# Sheet4.net
KiCad netlist of a schematic drawn in Altium Designer
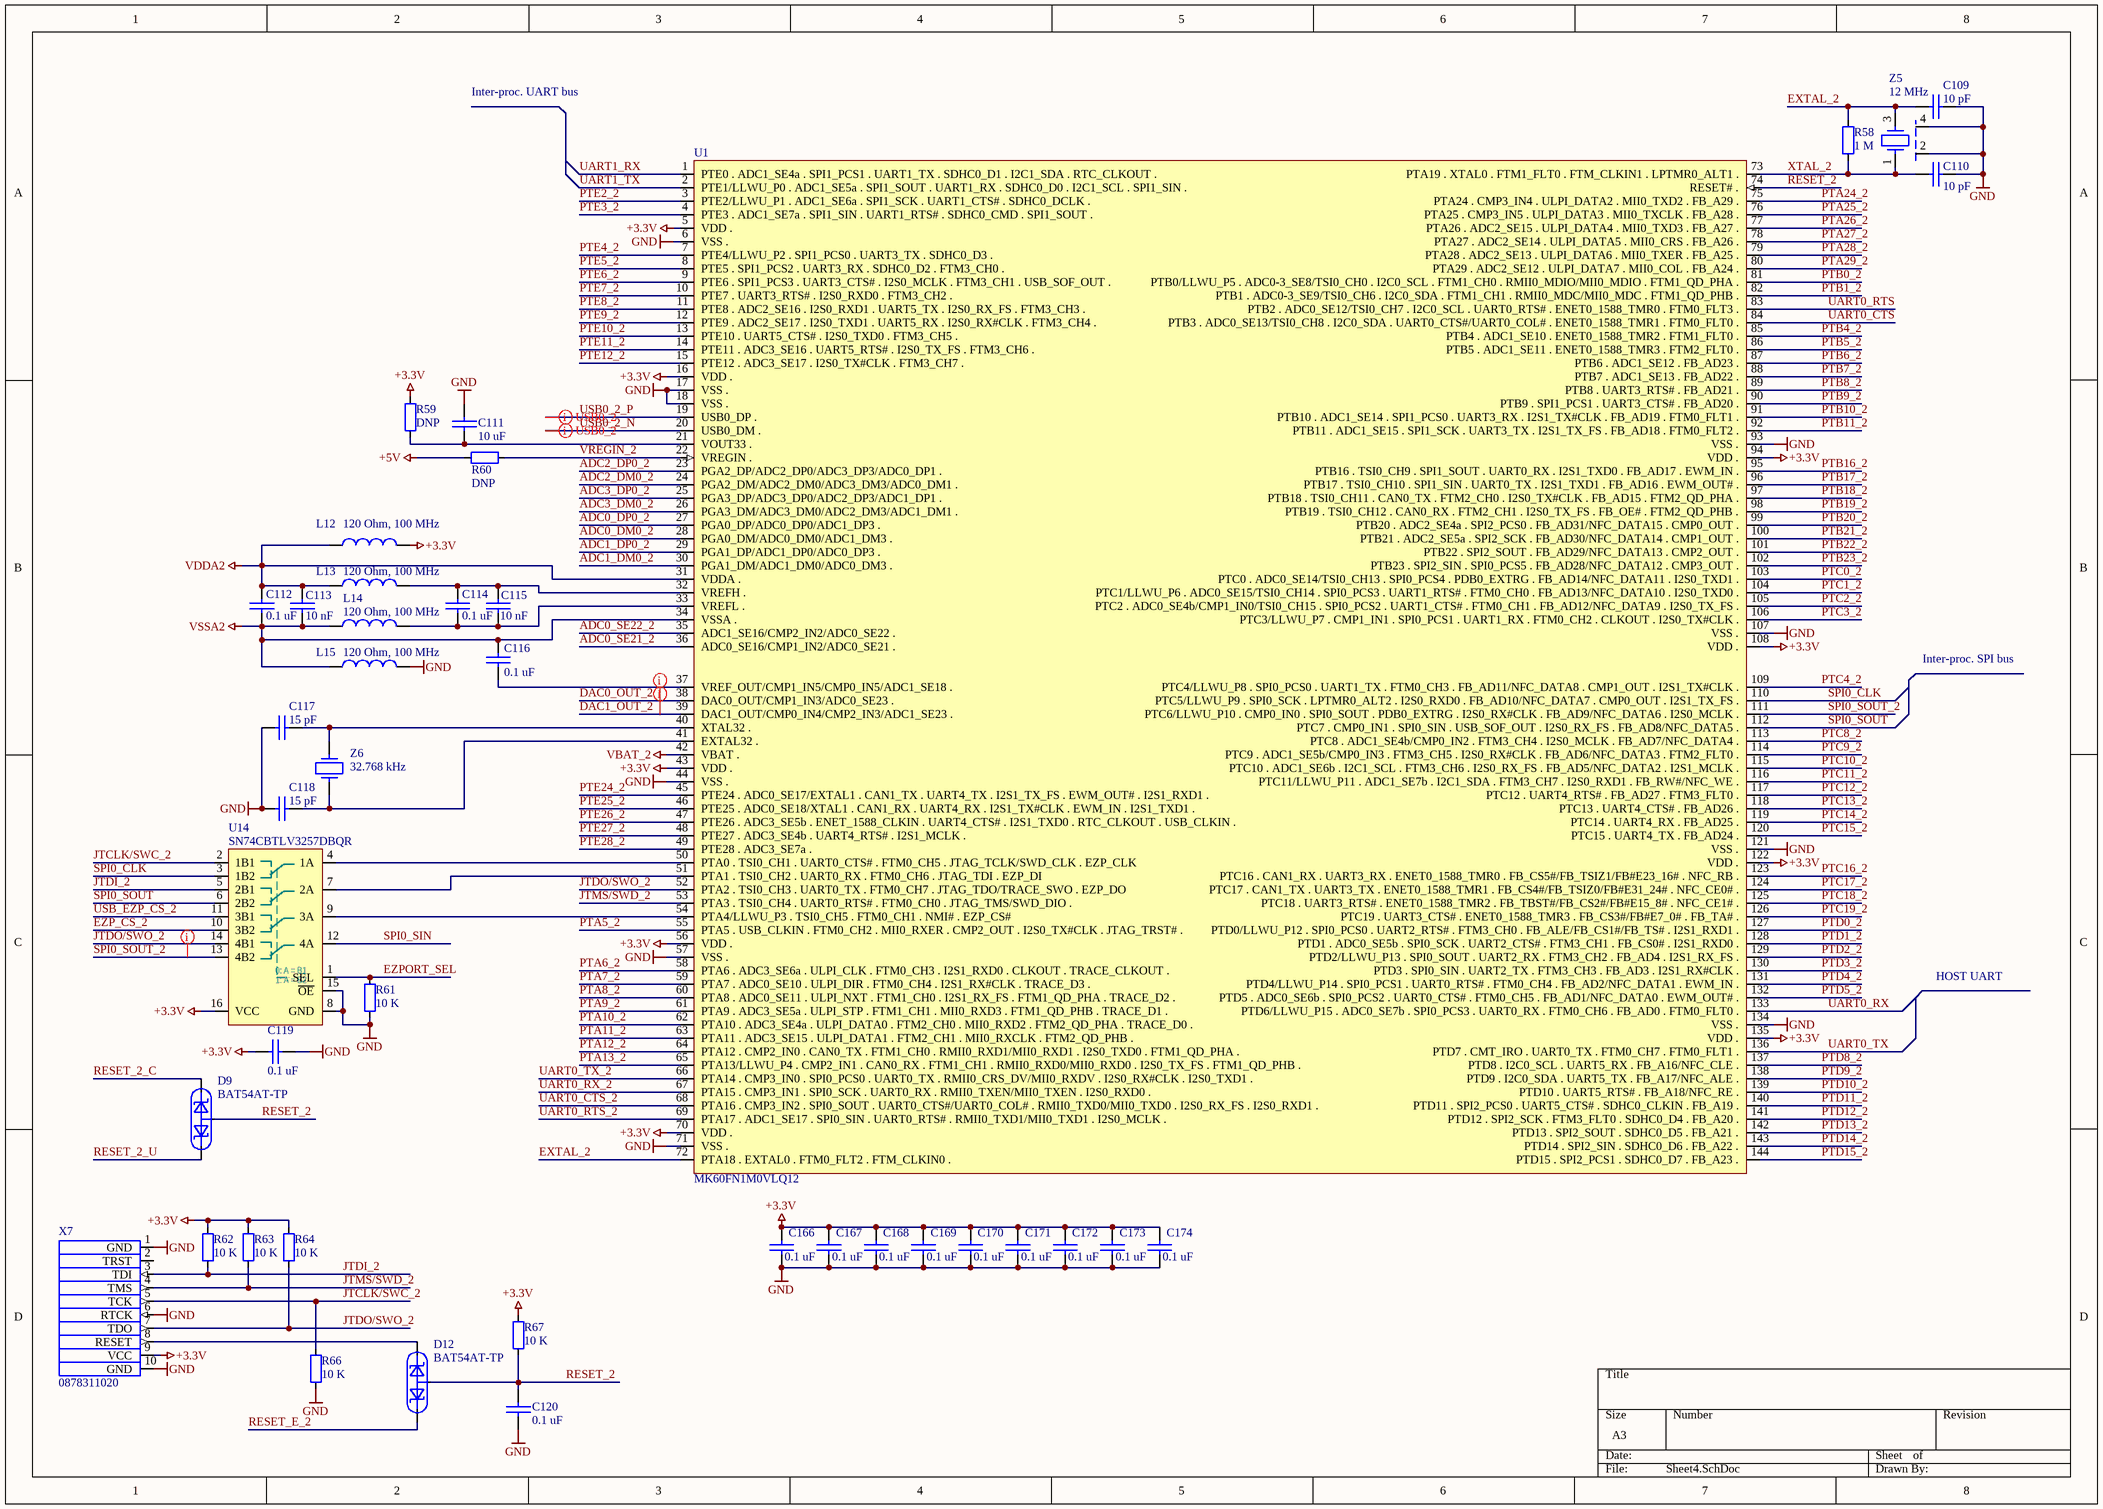
[diagram p0: Sheet4.SchDoc]

(export (version "E")
  (design (tool "Eeschema 10.0.6"))
  (components
    (comp (ref "C109")
      (value "10 pF")
      (footprint "1608[0603]")
      (description "10 pF, 50V, 5%, NP0, 0603 SMD MLC Capacitor")
      (fields (field (name "MANUFACTURER") "Kemet") (field (name "TOLERANCE") "5%"))
      (libsource (lib "ea_Capacitors") (part "CCPF010K0603"))
    )
    (comp (ref "C110")
      (value "10 pF")
      (footprint "1608[0603]")
      (description "10 pF, 50V, 5%, NP0, 0603 SMD MLC Capacitor")
      (fields (field (name "MANUFACTURER") "Kemet") (field (name "TOLERANCE") "5%"))
      (libsource (lib "ea_Capacitors") (part "CCPF010K0603"))
    )
    (comp (ref "C111")
      (value "10 uF")
      (footprint "2012[0805]")
      (description "10 uF, 16V, X5R, ±10%, 0805")
      (fields (field (name "MANUFACTURER") "TDK Corporation") (field (name "TOLERANCE") "±10%"))
      (libsource (lib "ea_Capacitors") (part "C2012X5R1C106K/0.85"))
    )
    (comp (ref "C112")
      (value "0.1 uF")
      (footprint "1005[0402]")
      (description "0.1 uF, 16V, 10%, X7R, 0402")
      (fields (field (name "TOLERANCE") "10%") (field (name "MANUFACTURER") "Murata"))
      (libsource (lib "ea_Capacitors") (part "GRM155R71C104KA88D"))
    )
    (comp (ref "C113")
      (value "10 nF")
      (footprint "1005[0402]")
      (description "10 nF, 16V, 10%, X7R, 0402")
      (fields (field (name "TOLERANCE") "10%") (field (name "MANUFACTURER") "SAMSUNG"))
      (libsource (lib "ea_Capacitors") (part "GRM155R71C103KA01D_1"))
    )
    (comp (ref "C114")
      (value "0.1 uF")
      (footprint "1005[0402]")
      (description "0.1 uF, 16V, 10%, X7R, 0402")
      (fields (field (name "TOLERANCE") "10%") (field (name "MANUFACTURER") "Murata"))
      (libsource (lib "ea_Capacitors") (part "GRM155R71C104KA88D"))
    )
    (comp (ref "C115")
      (value "10 nF")
      (footprint "1005[0402]")
      (description "10 nF, 16V, 10%, X7R, 0402")
      (fields (field (name "TOLERANCE") "10%") (field (name "MANUFACTURER") "SAMSUNG"))
      (libsource (lib "ea_Capacitors") (part "GRM155R71C103KA01D_1"))
    )
    (comp (ref "C116")
      (value "0.1 uF")
      (footprint "1608[0603]")
      (description "0.1 uF, 25V, 10% , X7R,  0603 SMD MLC Capacitor")
      (fields (field (name "TOLERANCE") "10%") (field (name "MANUFACTURER") "SAMSUNG"))
      (libsource (lib "ea_Capacitors") (part "CVNF100K0603-25"))
    )
    (comp (ref "C117")
      (value "15 pF")
      (footprint "1608[0603]")
      (description "15 pF, 50V, 5%, NP0, 0603 SMD MLC Capacitor")
      (fields (field (name "MANUFACTURER") "YAGEO AMERICA CORPORATION") (field (name "TOLERANCE") "5%"))
      (libsource (lib "ea_Capacitors") (part "CCPF015K0603"))
    )
    (comp (ref "C118")
      (value "15 pF")
      (footprint "1608[0603]")
      (description "15 pF, 50V, 5%, NP0, 0603 SMD MLC Capacitor")
      (fields (field (name "MANUFACTURER") "YAGEO AMERICA CORPORATION") (field (name "TOLERANCE") "5%"))
      (libsource (lib "ea_Capacitors") (part "CCPF015K0603"))
    )
    (comp (ref "C119")
      (value "0.1 uF")
      (footprint "1005[0402]")
      (description "0.1 uF, 16V, 10%, X7R, 0402")
      (fields (field (name "TOLERANCE") "10%") (field (name "MANUFACTURER") "Murata"))
      (libsource (lib "ea_Capacitors") (part "GRM155R71C104KA88D"))
    )
    (comp (ref "C120")
      (value "0.1 uF")
      (footprint "1005[0402]")
      (description "0.1 uF, 16V, 10%, X7R, 0402")
      (fields (field (name "TOLERANCE") "10%") (field (name "MANUFACTURER") "Murata"))
      (libsource (lib "ea_Capacitors") (part "GRM155R71C104KA88D"))
    )
    (comp (ref "C166")
      (value "0.1 uF")
      (footprint "1005[0402]")
      (description "0.1 uF, 16V, 10%, X7R, 0402")
      (fields (field (name "TOLERANCE") "10%") (field (name "MANUFACTURER") "Murata"))
      (libsource (lib "ea_Capacitors") (part "GRM155R71C104KA88D"))
    )
    (comp (ref "C167")
      (value "0.1 uF")
      (footprint "1005[0402]")
      (description "0.1 uF, 16V, 10%, X7R, 0402")
      (fields (field (name "TOLERANCE") "10%") (field (name "MANUFACTURER") "Murata"))
      (libsource (lib "ea_Capacitors") (part "GRM155R71C104KA88D"))
    )
    (comp (ref "C168")
      (value "0.1 uF")
      (footprint "1005[0402]")
      (description "0.1 uF, 16V, 10%, X7R, 0402")
      (fields (field (name "TOLERANCE") "10%") (field (name "MANUFACTURER") "Murata"))
      (libsource (lib "ea_Capacitors") (part "GRM155R71C104KA88D"))
    )
    (comp (ref "C169")
      (value "0.1 uF")
      (footprint "1005[0402]")
      (description "0.1 uF, 16V, 10%, X7R, 0402")
      (fields (field (name "TOLERANCE") "10%") (field (name "MANUFACTURER") "Murata"))
      (libsource (lib "ea_Capacitors") (part "GRM155R71C104KA88D"))
    )
    (comp (ref "C170")
      (value "0.1 uF")
      (footprint "1005[0402]")
      (description "0.1 uF, 16V, 10%, X7R, 0402")
      (fields (field (name "TOLERANCE") "10%") (field (name "MANUFACTURER") "Murata"))
      (libsource (lib "ea_Capacitors") (part "GRM155R71C104KA88D"))
    )
    (comp (ref "C171")
      (value "0.1 uF")
      (footprint "1005[0402]")
      (description "0.1 uF, 16V, 10%, X7R, 0402")
      (fields (field (name "TOLERANCE") "10%") (field (name "MANUFACTURER") "Murata"))
      (libsource (lib "ea_Capacitors") (part "GRM155R71C104KA88D"))
    )
    (comp (ref "C172")
      (value "0.1 uF")
      (footprint "1005[0402]")
      (description "0.1 uF, 16V, 10%, X7R, 0402")
      (fields (field (name "TOLERANCE") "10%") (field (name "MANUFACTURER") "Murata"))
      (libsource (lib "ea_Capacitors") (part "GRM155R71C104KA88D"))
    )
    (comp (ref "C173")
      (value "0.1 uF")
      (footprint "1005[0402]")
      (description "0.1 uF, 16V, 10%, X7R, 0402")
      (fields (field (name "TOLERANCE") "10%") (field (name "MANUFACTURER") "Murata"))
      (libsource (lib "ea_Capacitors") (part "GRM155R71C104KA88D"))
    )
    (comp (ref "C174")
      (value "0.1 uF")
      (footprint "1005[0402]")
      (description "0.1 uF, 16V, 10%, X7R, 0402")
      (fields (field (name "TOLERANCE") "10%") (field (name "MANUFACTURER") "Murata"))
      (libsource (lib "ea_Capacitors") (part "GRM155R71C104KA88D"))
    )
    (comp (ref "D9")
      (value "BAT54AT-TP")
      (footprint "SOT-523F")
      (description "Schottky Diode, 30 V, 200 mA, common anode, SOT523")
      (fields (field (name "MANUFACTURER") "Micro Commercial Co") (field (name "PARTNUM") "BAT54AT-TPDKR-ND"))
      (libsource (lib "ea_Diodes") (part "BAT54AT-TP"))
    )
    (comp (ref "D12")
      (value "BAT54AT-TP")
      (footprint "SOT-523F")
      (description "Schottky Diode, 30 V, 200 mA, common anode, SOT523")
      (fields (field (name "MANUFACTURER") "Micro Commercial Co") (field (name "PARTNUM") "BAT54AT-TPDKR-ND"))
      (libsource (lib "ea_Diodes") (part "BAT54AT-TP"))
    )
    (comp (ref "L12")
      (value "120 Ohm, 100 MHz")
      (footprint "1005[0402]")
      (description "Ferrite bead, 120 Ohm, 100 MHz,  1.2 A, 0.09 Ohm, 0402")
      (fields (field (name "MANUFACTURER") "TDK Corporation") (field (name "PARTNUM") "445-2981-1-ND"))
      (libsource (lib "ea_Inductors") (part "MPZ1005S121C"))
    )
    (comp (ref "L13")
      (value "120 Ohm, 100 MHz")
      (footprint "1005[0402]")
      (description "Ferrite bead, 120 Ohm, 100 MHz,  1.2 A, 0.09 Ohm, 0402")
      (fields (field (name "MANUFACTURER") "TDK Corporation") (field (name "PARTNUM") "445-2981-1-ND"))
      (libsource (lib "ea_Inductors") (part "MPZ1005S121C"))
    )
    (comp (ref "L14")
      (value "120 Ohm, 100 MHz")
      (footprint "1005[0402]")
      (description "Ferrite bead, 120 Ohm, 100 MHz,  1.2 A, 0.09 Ohm, 0402")
      (fields (field (name "MANUFACTURER") "TDK Corporation") (field (name "PARTNUM") "445-2981-1-ND"))
      (libsource (lib "ea_Inductors") (part "MPZ1005S121C"))
    )
    (comp (ref "L15")
      (value "120 Ohm, 100 MHz")
      (footprint "1005[0402]")
      (description "Ferrite bead, 120 Ohm, 100 MHz,  1.2 A, 0.09 Ohm, 0402")
      (fields (field (name "MANUFACTURER") "TDK Corporation") (field (name "PARTNUM") "445-2981-1-ND"))
      (libsource (lib "ea_Inductors") (part "MPZ1005S121C"))
    )
    (comp (ref "R58")
      (value "1 M")
      (footprint "0603")
      (description "1 M, 1%, 0603, SMD Resistor, Taped")
      (fields (field (name "MANUFACTURER") "YAGEO AMERICA CORPORATION") (field (name "TOLERANCE") "1%"))
      (libsource (lib "ea_Resistors") (part "RC0603FR-071ML"))
    )
    (comp (ref "R59")
      (value "DNP")
      (footprint "0603")
      (description "DNP, 0603")
      (fields (field (name "Comment") "DNP_0603"))
      (libsource (lib "") (part "DNP_0603_1"))
    )
    (comp (ref "R60")
      (value "DNP")
      (footprint "0603")
      (description "DNP, 0603")
      (fields (field (name "Comment") "DNP_0603"))
      (libsource (lib "ea_Resistors") (part "DNP_0603"))
    )
    (comp (ref "R61")
      (value "10 K")
      (footprint "0402")
      (description "10 K, 5%, 0402, SMD Resistor, Taped")
      (fields (field (name "MANUFACTURER") "Yageo") (field (name "TOLERANCE") "5%"))
      (libsource (lib "") (part "RC0402JR-0710KL_1"))
    )
    (comp (ref "R62")
      (value "10 K")
      (footprint "0402")
      (description "10 K, 5%, 0402, SMD Resistor, Taped")
      (fields (field (name "MANUFACTURER") "Yageo") (field (name "TOLERANCE") "5%"))
      (libsource (lib "ea_Resistors") (part "RC0402JR-0710KL"))
    )
    (comp (ref "R63")
      (value "10 K")
      (footprint "0402")
      (description "10 K, 5%, 0402, SMD Resistor, Taped")
      (fields (field (name "MANUFACTURER") "Yageo") (field (name "TOLERANCE") "5%"))
      (libsource (lib "ea_Resistors") (part "RC0402JR-0710KL"))
    )
    (comp (ref "R64")
      (value "10 K")
      (footprint "0402")
      (description "10 K, 5%, 0402, SMD Resistor, Taped")
      (fields (field (name "MANUFACTURER") "Yageo") (field (name "TOLERANCE") "5%"))
      (libsource (lib "ea_Resistors") (part "RC0402JR-0710KL"))
    )
    (comp (ref "R66")
      (value "10 K")
      (footprint "0402")
      (description "10 K, 5%, 0402, SMD Resistor, Taped")
      (fields (field (name "MANUFACTURER") "Yageo") (field (name "TOLERANCE") "5%"))
      (libsource (lib "ea_Resistors") (part "RC0402JR-0710KL"))
    )
    (comp (ref "R67")
      (value "10 K")
      (footprint "0402")
      (description "10 K, 5%, 0402, SMD Resistor, Taped")
      (fields (field (name "MANUFACTURER") "Yageo") (field (name "TOLERANCE") "5%"))
      (libsource (lib "ea_Resistors") (part "RC0402JR-0710KL"))
    )
    (comp (ref "U1")
      (value "MK60FN1M0VLQ12")
      (footprint "ea_TQFP:LQFP144")
      (description "MK60 Series 32 Bit 1 MB Flash 128 KB Ram 120 Mhz Microcontroller - LQFP-144")
      (fields (field (name "MANUFACTURER") "Freescale"))
      (libsource (lib "ea_IC_CPU") (part "MK60FN1M0VLQ12"))
    )
    (comp (ref "U14")
      (value "SN74CBTLV3257DBQR")
      (footprint "TI DBQ 16pin (R-PDSO-G16)")
      (description "LV DUAL FET MUX/DEMUX, 2.3..3.6V,  -40..85 C, 16SSOP")
      (fields (field (name "MANUFACTURER") "Texas Instruments") (field (name "PARTNUM") "296-9135-1-ND"))
      (libsource (lib "ea_IC_Logic") (part "SN74CBTLV3257DBQR"))
    )
    (comp (ref "X7")
      (value "0878311020")
      (footprint "878311020 MGRID WALL HDR SMD")
      (description "JTAG, CONN HEADER 10POS 2MM VERT SMD")
      (fields (field (name "MANUFACTURER") "Molex Inc") (field (name "PARTNUM") "WM18639-ND"))
      (libsource (lib "ea_Connectors") (part "0878321020"))
    )
    (comp (ref "Z5")
      (value "12 MHz")
      (footprint "DSX321G")
      (description "12 MHz, 8 pF, ±15ppm, -10...+75 С")
      (fields (field (name "MANUFACTURER") "NDK") (field (name "PARTNUM") "644-1047-1-ND"))
      (libsource (lib "ea_OSC_CLK_GEN") (part "NX3225SA-12.000MHZ-STD-CSR-1"))
    )
    (comp (ref "Z6")
      (value "32.768 kHz")
      (footprint "ABS10")
      (description "32.768 kHz, 12.5 pF, 70 kOhm, ±20ppm, -40°C ~ 80°C")
      (fields (field (name "MANUFACTURER") "Abracon Corporation") (field (name "PARTNUM") "535-9536-1-ND"))
      (libsource (lib "ea_OSC_CLK_GEN") (part "ABS10-32.768KHZ-T"))
    )
  )
  (nets
    (net (code "1") (name "+3.3V") (class "Default")
      (node (ref "C119") (pin "1") (pinfunction "1_1") (pintype "passive"))
      (node (ref "C166") (pin "2") (pinfunction "2_2") (pintype "passive"))
      (node (ref "C167") (pin "2") (pinfunction "2_2") (pintype "passive"))
      (node (ref "C168") (pin "2") (pinfunction "2_2") (pintype "passive"))
      (node (ref "C169") (pin "2") (pinfunction "2_2") (pintype "passive"))
      (node (ref "C170") (pin "2") (pinfunction "2_2") (pintype "passive"))
      (node (ref "C171") (pin "2") (pinfunction "2_2") (pintype "passive"))
      (node (ref "C172") (pin "2") (pinfunction "2_2") (pintype "passive"))
      (node (ref "C173") (pin "2") (pinfunction "2_2") (pintype "passive"))
      (node (ref "C174") (pin "2") (pinfunction "2_2") (pintype "passive"))
      (node (ref "L12") (pin "2") (pinfunction "2_2") (pintype "passive"))
      (node (ref "R59") (pin "1") (pinfunction "1_1") (pintype "passive"))
      (node (ref "R62") (pin "1") (pinfunction "1_1") (pintype "passive"))
      (node (ref "R63") (pin "1") (pinfunction "1_1") (pintype "passive"))
      (node (ref "R64") (pin "1") (pinfunction "1_1") (pintype "passive"))
      (node (ref "R67") (pin "1") (pinfunction "1_1") (pintype "passive"))
      (node (ref "U1") (pin "108") (pinfunction "VDD_._108") (pintype "power_in"))
      (node (ref "U1") (pin "122") (pinfunction "VDD_._122") (pintype "power_in"))
      (node (ref "U1") (pin "135") (pinfunction "VDD_._135") (pintype "power_in"))
      (node (ref "U1") (pin "16") (pinfunction "VDD_._16") (pintype "power_in"))
      (node (ref "U1") (pin "43") (pinfunction "VDD_._43") (pintype "power_in"))
      (node (ref "U1") (pin "5") (pinfunction "VDD_._5") (pintype "power_in"))
      (node (ref "U1") (pin "56") (pinfunction "VDD_._56") (pintype "power_in"))
      (node (ref "U1") (pin "70") (pinfunction "VDD_._70") (pintype "power_in"))
      (node (ref "U1") (pin "94") (pinfunction "VDD_._94") (pintype "power_in"))
      (node (ref "U14") (pin "16") (pinfunction "VCC_16") (pintype "passive"))
      (node (ref "X7") (pin "9") (pinfunction "VCC_9") (pintype "power_in"))
    )
    (net (code "2") (name "+5V") (class "Default")
      (node (ref "R60") (pin "1") (pinfunction "1_1") (pintype "passive"))
    )
    (net (code "3") (name "/ADC0_DM0_2") (class "Default")
      (node (ref "U1") (pin "28") (pinfunction "PGA0_DM/ADC0_DM0/ADC1_DM3_._28") (pintype "bidirectional"))
    )
    (net (code "4") (name "/ADC0_DP0_2") (class "Default")
      (node (ref "U1") (pin "27") (pinfunction "PGA0_DP/ADC0_DP0/ADC1_DP3_._27") (pintype "bidirectional"))
    )
    (net (code "5") (name "/ADC0_SE21_2") (class "Default")
      (node (ref "U1") (pin "36") (pinfunction "ADC0_SE16/CMP1_IN2/ADC0_SE21_._36") (pintype "bidirectional"))
    )
    (net (code "6") (name "/ADC0_SE22_2") (class "Default")
      (node (ref "U1") (pin "35") (pinfunction "ADC1_SE16/CMP2_IN2/ADC0_SE22_._35") (pintype "bidirectional"))
    )
    (net (code "7") (name "/ADC1_DM0_2") (class "Default")
      (node (ref "U1") (pin "30") (pinfunction "PGA1_DM/ADC1_DM0/ADC0_DM3_._30") (pintype "bidirectional"))
    )
    (net (code "8") (name "/ADC1_DP0_2") (class "Default")
      (node (ref "U1") (pin "29") (pinfunction "PGA1_DP/ADC1_DP0/ADC0_DP3_._29") (pintype "bidirectional"))
    )
    (net (code "9") (name "/ADC2_DM0_2") (class "Default")
      (node (ref "U1") (pin "24") (pinfunction "PGA2_DM/ADC2_DM0/ADC3_DM3/ADC0_DM1_._24") (pintype "bidirectional"))
    )
    (net (code "10") (name "/ADC2_DP0_2") (class "Default")
      (node (ref "U1") (pin "23") (pinfunction "PGA2_DP/ADC2_DP0/ADC3_DP3/ADC0_DP1_._23") (pintype "bidirectional"))
    )
    (net (code "11") (name "/ADC3_DM0_2") (class "Default")
      (node (ref "U1") (pin "26") (pinfunction "PGA3_DM/ADC3_DM0/ADC2_DM3/ADC1_DM1_._26") (pintype "bidirectional"))
    )
    (net (code "12") (name "/ADC3_DP0_2") (class "Default")
      (node (ref "U1") (pin "25") (pinfunction "PGA3_DP/ADC3_DP0/ADC2_DP3/ADC1_DP1_._25") (pintype "bidirectional"))
    )
    (net (code "13") (name "/DAC0_OUT_2") (class "Default")
      (node (ref "U1") (pin "38") (pinfunction "DAC0_OUT/CMP1_IN3/ADC0_SE23_._38") (pintype "bidirectional"))
    )
    (net (code "14") (name "/DAC1_OUT_2") (class "Default")
      (node (ref "U1") (pin "39") (pinfunction "DAC1_OUT/CMP0_IN4/CMP2_IN3/ADC1_SE23_._39") (pintype "bidirectional"))
    )
    (net (code "15") (name "/EXTAL_2") (class "Default")
      (node (ref "C109") (pin "1") (pinfunction "1_1") (pintype "passive"))
      (node (ref "R58") (pin "2") (pinfunction "2_2") (pintype "passive"))
      (node (ref "U1") (pin "72") (pinfunction "PTA18_._EXTAL0_._FTM0_FLT2_._FTM_CLKIN0_._72") (pintype "bidirectional"))
      (node (ref "Z5") (pin "3") (pinfunction "3_3") (pintype "passive"))
    )
    (net (code "16") (name "/EZPORT_SEL") (class "Default")
      (node (ref "R61") (pin "1") (pinfunction "1_1") (pintype "passive"))
      (node (ref "U14") (pin "1") (pinfunction "SEL_1") (pintype "passive"))
    )
    (net (code "17") (name "/EZP_CS_2") (class "Default")
      (node (ref "U14") (pin "10") (pinfunction "3B2_10") (pintype "passive"))
    )
    (net (code "18") (name "/JTCLK{slash}SWC_2") (class "Default")
      (node (ref "R66") (pin "1") (pinfunction "1_1") (pintype "passive"))
      (node (ref "U14") (pin "2") (pinfunction "1B1_2") (pintype "passive"))
      (node (ref "X7") (pin "5") (pinfunction "TCK_5") (pintype "output"))
    )
    (net (code "19") (name "/JTDI_2") (class "Default")
      (node (ref "R62") (pin "2") (pinfunction "2_2") (pintype "passive"))
      (node (ref "U14") (pin "5") (pinfunction "2B1_5") (pintype "passive"))
      (node (ref "X7") (pin "3") (pinfunction "TDI_3") (pintype "input"))
    )
    (net (code "20") (name "/JTDO{slash}SWO_2") (class "Default")
      (node (ref "R64") (pin "2") (pinfunction "2_2") (pintype "passive"))
      (node (ref "U1") (pin "52") (pinfunction "PTA2_._TSI0_CH3_._UART0_TX_._FTM0_CH7_._JTAG_TDO/TRACE_SWO_._EZP_DO_52") (pintype "bidirectional"))
      (node (ref "U14") (pin "14") (pinfunction "4B1_14") (pintype "passive"))
      (node (ref "X7") (pin "7") (pinfunction "TDO_7") (pintype "output"))
    )
    (net (code "21") (name "/JTMS{slash}SWD_2") (class "Default")
      (node (ref "R63") (pin "2") (pinfunction "2_2") (pintype "passive"))
      (node (ref "U1") (pin "53") (pinfunction "PTA3_._TSI0_CH4_._UART0_RTS#_._FTM0_CH0_._JTAG_TMS/SWD_DIO_._53") (pintype "bidirectional"))
      (node (ref "X7") (pin "4") (pinfunction "TMS_4") (pintype "output"))
    )
    (net (code "22") (name "/PTA5_2") (class "Default")
      (node (ref "U1") (pin "55") (pinfunction "PTA5_._USB_CLKIN_._FTM0_CH2_._MII0_RXER_._CMP2_OUT_._I2S0_TX#CLK_._JTAG_TRST#_._55") (pintype "bidirectional"))
    )
    (net (code "23") (name "/PTA6_2") (class "Default")
      (node (ref "U1") (pin "58") (pinfunction "PTA6_._ADC3_SE6a_._ULPI_CLK_._FTM0_CH3_._I2S1_RXD0_._CLKOUT_._TRACE_CLKOUT_._58") (pintype "bidirectional"))
    )
    (net (code "24") (name "/PTA7_2") (class "Default")
      (node (ref "U1") (pin "59") (pinfunction "PTA7_._ADC0_SE10_._ULPI_DIR_._FTM0_CH4_._I2S1_RX#CLK_._TRACE_D3_._59") (pintype "bidirectional"))
    )
    (net (code "25") (name "/PTA8_2") (class "Default")
      (node (ref "U1") (pin "60") (pinfunction "PTA8_._ADC0_SE11_._ULPI_NXT_._FTM1_CH0_._I2S1_RX_FS_._FTM1_QD_PHA_._TRACE_D2_._60") (pintype "bidirectional"))
    )
    (net (code "26") (name "/PTA9_2") (class "Default")
      (node (ref "U1") (pin "61") (pinfunction "PTA9_._ADC3_SE5a_._ULPI_STP_._FTM1_CH1_._MII0_RXD3_._FTM1_QD_PHB_._TRACE_D1_._61") (pintype "bidirectional"))
    )
    (net (code "27") (name "/PTA10_2") (class "Default")
      (node (ref "U1") (pin "62") (pinfunction "PTA10_._ADC3_SE4a_._ULPI_DATA0_._FTM2_CH0_._MII0_RXD2_._FTM2_QD_PHA_._TRACE_D0_._62") (pintype "bidirectional"))
    )
    (net (code "28") (name "/PTA11_2") (class "Default")
      (node (ref "U1") (pin "63") (pinfunction "PTA11_._ADC3_SE15_._ULPI_DATA1_._FTM2_CH1_._MII0_RXCLK_._FTM2_QD_PHB_._63") (pintype "bidirectional"))
    )
    (net (code "29") (name "/PTA12_2") (class "Default")
      (node (ref "U1") (pin "64") (pinfunction "PTA12_._CMP2_IN0_._CAN0_TX_._FTM1_CH0_._RMII0_RXD1/MII0_RXD1_._I2S0_TXD0_._FTM1_QD_PHA_._64") (pintype "bidirectional"))
    )
    (net (code "30") (name "/PTA13_2") (class "Default")
      (node (ref "U1") (pin "65") (pinfunction "PTA13/LLWU_P4_._CMP2_IN1_._CAN0_RX_._FTM1_CH1_._RMII0_RXD0/MII0_RXD0_._I2S0_TX_FS_._FTM1_QD_PHB_._65") (pintype "bidirectional"))
    )
    (net (code "31") (name "/PTA24_2") (class "Default")
      (node (ref "U1") (pin "75") (pinfunction "PTA24_._CMP3_IN4_._ULPI_DATA2_._MII0_TXD2_._FB_A29_._75") (pintype "bidirectional"))
    )
    (net (code "32") (name "/PTA25_2") (class "Default")
      (node (ref "U1") (pin "76") (pinfunction "PTA25_._CMP3_IN5_._ULPI_DATA3_._MII0_TXCLK_._FB_A28_._76") (pintype "bidirectional"))
    )
    (net (code "33") (name "/PTA26_2") (class "Default")
      (node (ref "U1") (pin "77") (pinfunction "PTA26_._ADC2_SE15_._ULPI_DATA4_._MII0_TXD3_._FB_A27_._77") (pintype "bidirectional"))
    )
    (net (code "34") (name "/PTA27_2") (class "Default")
      (node (ref "U1") (pin "78") (pinfunction "PTA27_._ADC2_SE14_._ULPI_DATA5_._MII0_CRS_._FB_A26_._78") (pintype "bidirectional"))
    )
    (net (code "35") (name "/PTA28_2") (class "Default")
      (node (ref "U1") (pin "79") (pinfunction "PTA28_._ADC2_SE13_._ULPI_DATA6_._MII0_TXER_._FB_A25_._79") (pintype "bidirectional"))
    )
    (net (code "36") (name "/PTA29_2") (class "Default")
      (node (ref "U1") (pin "80") (pinfunction "PTA29_._ADC2_SE12_._ULPI_DATA7_._MII0_COL_._FB_A24_._80") (pintype "bidirectional"))
    )
    (net (code "37") (name "/PTB0_2") (class "Default")
      (node (ref "U1") (pin "81") (pinfunction "PTB0/LLWU_P5_._ADC0-3_SE8/TSI0_CH0_._I2C0_SCL_._FTM1_CH0_._RMII0_MDIO/MII0_MDIO_._FTM1_QD_PHA_._81") (pintype "bidirectional"))
    )
    (net (code "38") (name "/PTB1_2") (class "Default")
      (node (ref "U1") (pin "82") (pinfunction "PTB1_._ADC0-3_SE9/TSI0_CH6_._I2C0_SDA_._FTM1_CH1_._RMII0_MDC/MII0_MDC_._FTM1_QD_PHB_._82") (pintype "bidirectional"))
    )
    (net (code "39") (name "/PTB4_2") (class "Default")
      (node (ref "U1") (pin "85") (pinfunction "PTB4_._ADC1_SE10_._ENET0_1588_TMR2_._FTM1_FLT0_._85") (pintype "bidirectional"))
    )
    (net (code "40") (name "/PTB5_2") (class "Default")
      (node (ref "U1") (pin "86") (pinfunction "PTB5_._ADC1_SE11_._ENET0_1588_TMR3_._FTM2_FLT0_._86") (pintype "bidirectional"))
    )
    (net (code "41") (name "/PTB6_2") (class "Default")
      (node (ref "U1") (pin "87") (pinfunction "PTB6_._ADC1_SE12_._FB_AD23_._87") (pintype "bidirectional"))
    )
    (net (code "42") (name "/PTB7_2") (class "Default")
      (node (ref "U1") (pin "88") (pinfunction "PTB7_._ADC1_SE13_._FB_AD22_._88") (pintype "bidirectional"))
    )
    (net (code "43") (name "/PTB8_2") (class "Default")
      (node (ref "U1") (pin "89") (pinfunction "PTB8_._UART3_RTS#_._FB_AD21_._89") (pintype "bidirectional"))
    )
    (net (code "44") (name "/PTB9_2") (class "Default")
      (node (ref "U1") (pin "90") (pinfunction "PTB9_._SPI1_PCS1_._UART3_CTS#_._FB_AD20_._90") (pintype "bidirectional"))
    )
    (net (code "45") (name "/PTB10_2") (class "Default")
      (node (ref "U1") (pin "91") (pinfunction "PTB10_._ADC1_SE14_._SPI1_PCS0_._UART3_RX_._I2S1_TX#CLK_._FB_AD19_._FTM0_FLT1_._91") (pintype "bidirectional"))
    )
    (net (code "46") (name "/PTB11_2") (class "Default")
      (node (ref "U1") (pin "92") (pinfunction "PTB11_._ADC1_SE15_._SPI1_SCK_._UART3_TX_._I2S1_TX_FS_._FB_AD18_._FTM0_FLT2_._92") (pintype "bidirectional"))
    )
    (net (code "47") (name "/PTB16_2") (class "Default")
      (node (ref "U1") (pin "95") (pinfunction "PTB16_._TSI0_CH9_._SPI1_SOUT_._UART0_RX_._I2S1_TXD0_._FB_AD17_._EWM_IN_._95") (pintype "bidirectional"))
    )
    (net (code "48") (name "/PTB17_2") (class "Default")
      (node (ref "U1") (pin "96") (pinfunction "PTB17_._TSI0_CH10_._SPI1_SIN_._UART0_TX_._I2S1_TXD1_._FB_AD16_._EWM_OUT#_._96") (pintype "bidirectional"))
    )
    (net (code "49") (name "/PTB18_2") (class "Default")
      (node (ref "U1") (pin "97") (pinfunction "PTB18_._TSI0_CH11_._CAN0_TX_._FTM2_CH0_._I2S0_TX#CLK_._FB_AD15_._FTM2_QD_PHA_._97") (pintype "bidirectional"))
    )
    (net (code "50") (name "/PTB19_2") (class "Default")
      (node (ref "U1") (pin "98") (pinfunction "PTB19_._TSI0_CH12_._CAN0_RX_._FTM2_CH1_._I2S0_TX_FS_._FB_OE#_._FTM2_QD_PHB_._98") (pintype "bidirectional"))
    )
    (net (code "51") (name "/PTB20_2") (class "Default")
      (node (ref "U1") (pin "99") (pinfunction "PTB20_._ADC2_SE4a_._SPI2_PCS0_._FB_AD31/NFC_DATA15_._CMP0_OUT_._99") (pintype "bidirectional"))
    )
    (net (code "52") (name "/PTB21_2") (class "Default")
      (node (ref "U1") (pin "100") (pinfunction "PTB21_._ADC2_SE5a_._SPI2_SCK_._FB_AD30/NFC_DATA14_._CMP1_OUT_._100") (pintype "bidirectional"))
    )
    (net (code "53") (name "/PTB22_2") (class "Default")
      (node (ref "U1") (pin "101") (pinfunction "PTB22_._SPI2_SOUT_._FB_AD29/NFC_DATA13_._CMP2_OUT_._101") (pintype "bidirectional"))
    )
    (net (code "54") (name "/PTB23_2") (class "Default")
      (node (ref "U1") (pin "102") (pinfunction "PTB23_._SPI2_SIN_._SPI0_PCS5_._FB_AD28/NFC_DATA12_._CMP3_OUT_._102") (pintype "bidirectional"))
    )
    (net (code "55") (name "/PTC0_2") (class "Default")
      (node (ref "U1") (pin "103") (pinfunction "PTC0_._ADC0_SE14/TSI0_CH13_._SPI0_PCS4_._PDB0_EXTRG_._FB_AD14/NFC_DATA11_._I2S0_TXD1_._103") (pintype "bidirectional"))
    )
    (net (code "56") (name "/PTC1_2") (class "Default")
      (node (ref "U1") (pin "104") (pinfunction "PTC1/LLWU_P6_._ADC0_SE15/TSI0_CH14_._SPI0_PCS3_._UART1_RTS#_._FTM0_CH0_._FB_AD13/NFC_DATA10_._I2S0_TXD0_._104") (pintype "bidirectional"))
    )
    (net (code "57") (name "/PTC2_2") (class "Default")
      (node (ref "U1") (pin "105") (pinfunction "PTC2_._ADC0_SE4b/CMP1_IN0/TSI0_CH15_._SPI0_PCS2_._UART1_CTS#_._FTM0_CH1_._FB_AD12/NFC_DATA9_._I2S0_TX_FS_._105") (pintype "bidirectional"))
    )
    (net (code "58") (name "/PTC3_2") (class "Default")
      (node (ref "U1") (pin "106") (pinfunction "PTC3/LLWU_P7_._CMP1_IN1_._SPI0_PCS1_._UART1_RX_._FTM0_CH2_._CLKOUT_._I2S0_TX#CLK_._106") (pintype "bidirectional"))
    )
    (net (code "59") (name "/PTC4_2") (class "Default")
      (node (ref "U1") (pin "109") (pinfunction "PTC4/LLWU_P8_._SPI0_PCS0_._UART1_TX_._FTM0_CH3_._FB_AD11/NFC_DATA8_._CMP1_OUT_._I2S1_TX#CLK_._109") (pintype "bidirectional"))
    )
    (net (code "60") (name "/PTC8_2") (class "Default")
      (node (ref "U1") (pin "113") (pinfunction "PTC8_._ADC1_SE4b/CMP0_IN2_._FTM3_CH4_._I2S0_MCLK_._FB_AD7/NFC_DATA4_._113") (pintype "bidirectional"))
    )
    (net (code "61") (name "/PTC9_2") (class "Default")
      (node (ref "U1") (pin "114") (pinfunction "PTC9_._ADC1_SE5b/CMP0_IN3_._FTM3_CH5_._I2S0_RX#CLK_._FB_AD6/NFC_DATA3_._FTM2_FLT0_._114") (pintype "bidirectional"))
    )
    (net (code "62") (name "/PTC10_2") (class "Default")
      (node (ref "U1") (pin "115") (pinfunction "PTC10_._ADC1_SE6b_._I2C1_SCL_._FTM3_CH6_._I2S0_RX_FS_._FB_AD5/NFC_DATA2_._I2S1_MCLK_._115") (pintype "bidirectional"))
    )
    (net (code "63") (name "/PTC11_2") (class "Default")
      (node (ref "U1") (pin "116") (pinfunction "PTC11/LLWU_P11_._ADC1_SE7b_._I2C1_SDA_._FTM3_CH7_._I2S0_RXD1_._FB_RW#/NFC_WE_._116") (pintype "bidirectional"))
    )
    (net (code "64") (name "/PTC12_2") (class "Default")
      (node (ref "U1") (pin "117") (pinfunction "PTC12_._UART4_RTS#_._FB_AD27_._FTM3_FLT0_._117") (pintype "bidirectional"))
    )
    (net (code "65") (name "/PTC13_2") (class "Default")
      (node (ref "U1") (pin "118") (pinfunction "PTC13_._UART4_CTS#_._FB_AD26_._118") (pintype "bidirectional"))
    )
    (net (code "66") (name "/PTC14_2") (class "Default")
      (node (ref "U1") (pin "119") (pinfunction "PTC14_._UART4_RX_._FB_AD25_._119") (pintype "bidirectional"))
    )
    (net (code "67") (name "/PTC15_2") (class "Default")
      (node (ref "U1") (pin "120") (pinfunction "PTC15_._UART4_TX_._FB_AD24_._120") (pintype "bidirectional"))
    )
    (net (code "68") (name "/PTC16_2") (class "Default")
      (node (ref "U1") (pin "123") (pinfunction "PTC16_._CAN1_RX_._UART3_RX_._ENET0_1588_TMR0_._FB_CS5#/FB_TSIZ1/FB#E23_16#_._NFC_RB_._123") (pintype "bidirectional"))
    )
    (net (code "69") (name "/PTC17_2") (class "Default")
      (node (ref "U1") (pin "124") (pinfunction "PTC17_._CAN1_TX_._UART3_TX_._ENET0_1588_TMR1_._FB_CS4#/FB_TSIZ0/FB#E31_24#_._NFC_CE0#_._124") (pintype "bidirectional"))
    )
    (net (code "70") (name "/PTC18_2") (class "Default")
      (node (ref "U1") (pin "125") (pinfunction "PTC18_._UART3_RTS#_._ENET0_1588_TMR2_._FB_TBST#/FB_CS2#/FB#E15_8#_._NFC_CE1#_._125") (pintype "bidirectional"))
    )
    (net (code "71") (name "/PTC19_2") (class "Default")
      (node (ref "U1") (pin "126") (pinfunction "PTC19_._UART3_CTS#_._ENET0_1588_TMR3_._FB_CS3#/FB#E7_0#_._FB_TA#_._126") (pintype "bidirectional"))
    )
    (net (code "72") (name "/PTD0_2") (class "Default")
      (node (ref "U1") (pin "127") (pinfunction "PTD0/LLWU_P12_._SPI0_PCS0_._UART2_RTS#_._FTM3_CH0_._FB_ALE/FB_CS1#/FB_TS#_._I2S1_RXD1_._127") (pintype "bidirectional"))
    )
    (net (code "73") (name "/PTD1_2") (class "Default")
      (node (ref "U1") (pin "128") (pinfunction "PTD1_._ADC0_SE5b_._SPI0_SCK_._UART2_CTS#_._FTM3_CH1_._FB_CS0#_._I2S1_RXD0_._128") (pintype "bidirectional"))
    )
    (net (code "74") (name "/PTD2_2") (class "Default")
      (node (ref "U1") (pin "129") (pinfunction "PTD2/LLWU_P13_._SPI0_SOUT_._UART2_RX_._FTM3_CH2_._FB_AD4_._I2S1_RX_FS_._129") (pintype "bidirectional"))
    )
    (net (code "75") (name "/PTD3_2") (class "Default")
      (node (ref "U1") (pin "130") (pinfunction "PTD3_._SPI0_SIN_._UART2_TX_._FTM3_CH3_._FB_AD3_._I2S1_RX#CLK_._130") (pintype "bidirectional"))
    )
    (net (code "76") (name "/PTD4_2") (class "Default")
      (node (ref "U1") (pin "131") (pinfunction "PTD4/LLWU_P14_._SPI0_PCS1_._UART0_RTS#_._FTM0_CH4_._FB_AD2/NFC_DATA1_._EWM_IN_._131") (pintype "bidirectional"))
    )
    (net (code "77") (name "/PTD5_2") (class "Default")
      (node (ref "U1") (pin "132") (pinfunction "PTD5_._ADC0_SE6b_._SPI0_PCS2_._UART0_CTS#_._FTM0_CH5_._FB_AD1/NFC_DATA0_._EWM_OUT#_._132") (pintype "bidirectional"))
    )
    (net (code "78") (name "/PTD8_2") (class "Default")
      (node (ref "U1") (pin "137") (pinfunction "PTD8_._I2C0_SCL_._UART5_RX_._FB_A16/NFC_CLE_._137") (pintype "bidirectional"))
    )
    (net (code "79") (name "/PTD9_2") (class "Default")
      (node (ref "U1") (pin "138") (pinfunction "PTD9_._I2C0_SDA_._UART5_TX_._FB_A17/NFC_ALE_._138") (pintype "bidirectional"))
    )
    (net (code "80") (name "/PTD10_2") (class "Default")
      (node (ref "U1") (pin "139") (pinfunction "PTD10_._UART5_RTS#_._FB_A18/NFC_RE_._139") (pintype "bidirectional"))
    )
    (net (code "81") (name "/PTD11_2") (class "Default")
      (node (ref "U1") (pin "140") (pinfunction "PTD11_._SPI2_PCS0_._UART5_CTS#_._SDHC0_CLKIN_._FB_A19_._140") (pintype "bidirectional"))
    )
    (net (code "82") (name "/PTD12_2") (class "Default")
      (node (ref "U1") (pin "141") (pinfunction "PTD12_._SPI2_SCK_._FTM3_FLT0_._SDHC0_D4_._FB_A20_._141") (pintype "bidirectional"))
    )
    (net (code "83") (name "/PTD13_2") (class "Default")
      (node (ref "U1") (pin "142") (pinfunction "PTD13_._SPI2_SOUT_._SDHC0_D5_._FB_A21_._142") (pintype "bidirectional"))
    )
    (net (code "84") (name "/PTD14_2") (class "Default")
      (node (ref "U1") (pin "143") (pinfunction "PTD14_._SPI2_SIN_._SDHC0_D6_._FB_A22_._143") (pintype "bidirectional"))
    )
    (net (code "85") (name "/PTD15_2") (class "Default")
      (node (ref "U1") (pin "144") (pinfunction "PTD15_._SPI2_PCS1_._SDHC0_D7_._FB_A23_._144") (pintype "bidirectional"))
    )
    (net (code "86") (name "/PTE2_2") (class "Default")
      (node (ref "U1") (pin "3") (pinfunction "PTE2/LLWU_P1_._ADC1_SE6a_._SPI1_SCK_._UART1_CTS#_._SDHC0_DCLK_._3") (pintype "bidirectional"))
    )
    (net (code "87") (name "/PTE3_2") (class "Default")
      (node (ref "U1") (pin "4") (pinfunction "PTE3_._ADC1_SE7a_._SPI1_SIN_._UART1_RTS#_._SDHC0_CMD_._SPI1_SOUT_._4") (pintype "bidirectional"))
    )
    (net (code "88") (name "/PTE4_2") (class "Default")
      (node (ref "U1") (pin "7") (pinfunction "PTE4/LLWU_P2_._SPI1_PCS0_._UART3_TX_._SDHC0_D3_._7") (pintype "bidirectional"))
    )
    (net (code "89") (name "/PTE5_2") (class "Default")
      (node (ref "U1") (pin "8") (pinfunction "PTE5_._SPI1_PCS2_._UART3_RX_._SDHC0_D2_._FTM3_CH0_._8") (pintype "bidirectional"))
    )
    (net (code "90") (name "/PTE6_2") (class "Default")
      (node (ref "U1") (pin "9") (pinfunction "PTE6_._SPI1_PCS3_._UART3_CTS#_._I2S0_MCLK_._FTM3_CH1_._USB_SOF_OUT_._9") (pintype "bidirectional"))
    )
    (net (code "91") (name "/PTE7_2") (class "Default")
      (node (ref "U1") (pin "10") (pinfunction "PTE7_._UART3_RTS#_._I2S0_RXD0_._FTM3_CH2_._10") (pintype "bidirectional"))
    )
    (net (code "92") (name "/PTE8_2") (class "Default")
      (node (ref "U1") (pin "11") (pinfunction "PTE8_._ADC2_SE16_._I2S0_RXD1_._UART5_TX_._I2S0_RX_FS_._FTM3_CH3_._11") (pintype "bidirectional"))
    )
    (net (code "93") (name "/PTE9_2") (class "Default")
      (node (ref "U1") (pin "12") (pinfunction "PTE9_._ADC2_SE17_._I2S0_TXD1_._UART5_RX_._I2S0_RX#CLK_._FTM3_CH4_._12") (pintype "bidirectional"))
    )
    (net (code "94") (name "/PTE10_2") (class "Default")
      (node (ref "U1") (pin "13") (pinfunction "PTE10_._UART5_CTS#_._I2S0_TXD0_._FTM3_CH5_._13") (pintype "bidirectional"))
    )
    (net (code "95") (name "/PTE11_2") (class "Default")
      (node (ref "U1") (pin "14") (pinfunction "PTE11_._ADC3_SE16_._UART5_RTS#_._I2S0_TX_FS_._FTM3_CH6_._14") (pintype "bidirectional"))
    )
    (net (code "96") (name "/PTE12_2") (class "Default")
      (node (ref "U1") (pin "15") (pinfunction "PTE12_._ADC3_SE17_._I2S0_TX#CLK_._FTM3_CH7_._15") (pintype "bidirectional"))
    )
    (net (code "97") (name "/PTE24_2") (class "Default")
      (node (ref "U1") (pin "45") (pinfunction "PTE24_._ADC0_SE17/EXTAL1_._CAN1_TX_._UART4_TX_._I2S1_TX_FS_._EWM_OUT#_._I2S1_RXD1_._45") (pintype "bidirectional"))
    )
    (net (code "98") (name "/PTE25_2") (class "Default")
      (node (ref "U1") (pin "46") (pinfunction "PTE25_._ADC0_SE18/XTAL1_._CAN1_RX_._UART4_RX_._I2S1_TX#CLK_._EWM_IN_._I2S1_TXD1_._46") (pintype "bidirectional"))
    )
    (net (code "99") (name "/PTE26_2") (class "Default")
      (node (ref "U1") (pin "47") (pinfunction "PTE26_._ADC3_SE5b_._ENET_1588_CLKIN_._UART4_CTS#_._I2S1_TXD0_._RTC_CLKOUT_._USB_CLKIN_._47") (pintype "bidirectional"))
    )
    (net (code "100") (name "/PTE27_2") (class "Default")
      (node (ref "U1") (pin "48") (pinfunction "PTE27_._ADC3_SE4b_._UART4_RTS#_._I2S1_MCLK_._48") (pintype "bidirectional"))
    )
    (net (code "101") (name "/PTE28_2") (class "Default")
      (node (ref "U1") (pin "49") (pinfunction "PTE28_._ADC3_SE7a_._49") (pintype "bidirectional"))
    )
    (net (code "102") (name "/RESET_2") (class "Default")
      (node (ref "C120") (pin "1") (pinfunction "1_1") (pintype "passive"))
      (node (ref "D12") (pin "3") (pintype "passive"))
      (node (ref "D9") (pin "3") (pintype "passive"))
      (node (ref "R67") (pin "2") (pinfunction "2_2") (pintype "passive"))
      (node (ref "U1") (pin "74") (pinfunction "RESET#_._74") (pintype "input"))
    )
    (net (code "103") (name "/RESET_2_C") (class "Default") (node (ref "D9") (pin "1") (pintype "passive")))
    (net (code "104") (name "/RESET_2_U") (class "Default") (node (ref "D9") (pin "2") (pintype "passive")))
    (net (code "105") (name "/RESET_E_2") (class "Default") (node (ref "D12") (pin "2") (pintype "passive")))
    (net (code "106") (name "/SPI0_CLK") (class "Default")
      (node (ref "U1") (pin "110") (pinfunction "PTC5/LLWU_P9_._SPI0_SCK_._LPTMR0_ALT2_._I2S0_RXD0_._FB_AD10/NFC_DATA7_._CMP0_OUT_._I2S1_TX_FS_._110") (pintype "bidirectional"))
      (node (ref "U14") (pin "3") (pinfunction "1B2_3") (pintype "passive"))
    )
    (net (code "107") (name "/SPI0_SIN") (class "Default")
      (node (ref "U14") (pin "12") (pinfunction "4A_12") (pintype "passive"))
    )
    (net (code "108") (name "/SPI0_SOUT") (class "Default")
      (node (ref "U1") (pin "112") (pinfunction "PTC7_._CMP0_IN1_._SPI0_SIN_._USB_SOF_OUT_._I2S0_RX_FS_._FB_AD8/NFC_DATA5_._112") (pintype "bidirectional"))
      (node (ref "U14") (pin "6") (pinfunction "2B2_6") (pintype "passive"))
    )
    (net (code "109") (name "/SPI0_SOUT_2") (class "Default")
      (node (ref "U1") (pin "111") (pinfunction "PTC6/LLWU_P10_._CMP0_IN0_._SPI0_SOUT_._PDB0_EXTRG_._I2S0_RX#CLK_._FB_AD9/NFC_DATA6_._I2S0_MCLK_._111") (pintype "bidirectional"))
      (node (ref "U14") (pin "13") (pinfunction "4B2_13") (pintype "passive"))
    )
    (net (code "110") (name "/UART0_CTS") (class "Default")
      (node (ref "U1") (pin "84") (pinfunction "PTB3_._ADC0_SE13/TSI0_CH8_._I2C0_SDA_._UART0_CTS#/UART0_COL#_._ENET0_1588_TMR1_._FTM0_FLT0_._84") (pintype "bidirectional"))
    )
    (net (code "111") (name "/UART0_CTS_2") (class "Default")
      (node (ref "U1") (pin "68") (pinfunction "PTA16_._CMP3_IN2_._SPI0_SOUT_._UART0_CTS#/UART0_COL#_._RMII0_TXD0/MII0_TXD0_._I2S0_RX_FS_._I2S0_RXD1_._68") (pintype "bidirectional"))
    )
    (net (code "112") (name "/UART0_RTS") (class "Default")
      (node (ref "U1") (pin "83") (pinfunction "PTB2_._ADC0_SE12/TSI0_CH7_._I2C0_SCL_._UART0_RTS#_._ENET0_1588_TMR0_._FTM0_FLT3_._83") (pintype "bidirectional"))
    )
    (net (code "113") (name "/UART0_RTS_2") (class "Default")
      (node (ref "U1") (pin "69") (pinfunction "PTA17_._ADC1_SE17_._SPI0_SIN_._UART0_RTS#_._RMII0_TXD1/MII0_TXD1_._I2S0_MCLK_._69") (pintype "bidirectional"))
    )
    (net (code "114") (name "/UART0_RX") (class "Default")
      (node (ref "U1") (pin "133") (pinfunction "PTD6/LLWU_P15_._ADC0_SE7b_._SPI0_PCS3_._UART0_RX_._FTM0_CH6_._FB_AD0_._FTM0_FLT0_._133") (pintype "bidirectional"))
    )
    (net (code "115") (name "/UART0_RX_2") (class "Default")
      (node (ref "U1") (pin "67") (pinfunction "PTA15_._CMP3_IN1_._SPI0_SCK_._UART0_RX_._RMII0_TXEN/MII0_TXEN_._I2S0_RXD0_._67") (pintype "bidirectional"))
    )
    (net (code "116") (name "/UART0_TX") (class "Default")
      (node (ref "U1") (pin "136") (pinfunction "PTD7_._CMT_IRO_._UART0_TX_._FTM0_CH7_._FTM0_FLT1_._136") (pintype "bidirectional"))
    )
    (net (code "117") (name "/UART0_TX_2") (class "Default")
      (node (ref "U1") (pin "66") (pinfunction "PTA14_._CMP3_IN0_._SPI0_PCS0_._UART0_TX_._RMII0_CRS_DV/MII0_RXDV_._I2S0_RX#CLK_._I2S0_TXD1_._66") (pintype "bidirectional"))
    )
    (net (code "118") (name "/UART1_RX") (class "Default")
      (node (ref "U1") (pin "1") (pinfunction "PTE0_._ADC1_SE4a_._SPI1_PCS1_._UART1_TX_._SDHC0_D1_._I2C1_SDA_._RTC_CLKOUT_._1") (pintype "bidirectional"))
    )
    (net (code "119") (name "/UART1_TX") (class "Default")
      (node (ref "U1") (pin "2") (pinfunction "PTE1/LLWU_P0_._ADC1_SE5a_._SPI1_SOUT_._UART1_RX_._SDHC0_D0_._I2C1_SCL_._SPI1_SIN_._2") (pintype "bidirectional"))
    )
    (net (code "120") (name "/USB0_2_N") (class "Default")
      (node (ref "U1") (pin "20") (pinfunction "USB0_DM_._20") (pintype "bidirectional"))
    )
    (net (code "121") (name "/USB0_2_P") (class "Default")
      (node (ref "U1") (pin "19") (pinfunction "USB0_DP_._19") (pintype "bidirectional"))
    )
    (net (code "122") (name "/USB_EZP_CS_2") (class "Default")
      (node (ref "U14") (pin "11") (pinfunction "3B1_11") (pintype "passive"))
    )
    (net (code "123") (name "/VREGIN_2") (class "Default")
      (node (ref "R60") (pin "2") (pinfunction "2_2") (pintype "passive"))
      (node (ref "U1") (pin "22") (pinfunction "VREGIN_._22") (pintype "input"))
    )
    (net (code "124") (name "/XTAL_2") (class "Default")
      (node (ref "C110") (pin "1") (pinfunction "1_1") (pintype "passive"))
      (node (ref "R58") (pin "1") (pinfunction "1_1") (pintype "passive"))
      (node (ref "U1") (pin "73") (pinfunction "PTA19_._XTAL0_._FTM1_FLT0_._FTM_CLKIN1_._LPTMR0_ALT1_._73") (pintype "bidirectional"))
      (node (ref "Z5") (pin "1") (pinfunction "1_1") (pintype "passive"))
    )
    (net (code "125") (name "GND") (class "Default")
      (node (ref "C109") (pin "2") (pinfunction "2_2") (pintype "passive"))
      (node (ref "C110") (pin "2") (pinfunction "2_2") (pintype "passive"))
      (node (ref "C111") (pin "2") (pinfunction "2_2") (pintype "passive"))
      (node (ref "C117") (pin "2") (pinfunction "2_2") (pintype "passive"))
      (node (ref "C118") (pin "2") (pinfunction "2_2") (pintype "passive"))
      (node (ref "C119") (pin "2") (pinfunction "2_2") (pintype "passive"))
      (node (ref "C120") (pin "2") (pinfunction "2_2") (pintype "passive"))
      (node (ref "C166") (pin "1") (pinfunction "1_1") (pintype "passive"))
      (node (ref "C167") (pin "1") (pinfunction "1_1") (pintype "passive"))
      (node (ref "C168") (pin "1") (pinfunction "1_1") (pintype "passive"))
      (node (ref "C169") (pin "1") (pinfunction "1_1") (pintype "passive"))
      (node (ref "C170") (pin "1") (pinfunction "1_1") (pintype "passive"))
      (node (ref "C171") (pin "1") (pinfunction "1_1") (pintype "passive"))
      (node (ref "C172") (pin "1") (pinfunction "1_1") (pintype "passive"))
      (node (ref "C173") (pin "1") (pinfunction "1_1") (pintype "passive"))
      (node (ref "C174") (pin "1") (pinfunction "1_1") (pintype "passive"))
      (node (ref "L15") (pin "2") (pinfunction "2_2") (pintype "passive"))
      (node (ref "R61") (pin "2") (pinfunction "2_2") (pintype "passive"))
      (node (ref "R66") (pin "2") (pinfunction "2_2") (pintype "passive"))
      (node (ref "U1") (pin "107") (pinfunction "VSS_._107") (pintype "power_in"))
      (node (ref "U1") (pin "121") (pinfunction "VSS_._121") (pintype "power_in"))
      (node (ref "U1") (pin "134") (pinfunction "VSS_._134") (pintype "power_in"))
      (node (ref "U1") (pin "17") (pinfunction "VSS_._17") (pintype "power_in"))
      (node (ref "U1") (pin "18") (pinfunction "VSS_._18") (pintype "power_in"))
      (node (ref "U1") (pin "44") (pinfunction "VSS_._44") (pintype "power_in"))
      (node (ref "U1") (pin "57") (pinfunction "VSS_._57") (pintype "power_in"))
      (node (ref "U1") (pin "6") (pinfunction "VSS_._6") (pintype "power_in"))
      (node (ref "U1") (pin "71") (pinfunction "VSS_._71") (pintype "power_in"))
      (node (ref "U1") (pin "93") (pinfunction "VSS_._93") (pintype "power_in"))
      (node (ref "U14") (pin "15") (pinfunction "~{OE}_15") (pintype "passive"))
      (node (ref "U14") (pin "8") (pinfunction "GND_8") (pintype "passive"))
      (node (ref "X7") (pin "1") (pinfunction "GND_1") (pintype "power_in"))
      (node (ref "X7") (pin "10") (pinfunction "GND_10") (pintype "power_in"))
      (node (ref "X7") (pin "6") (pinfunction "RTCK_6") (pintype "input"))
      (node (ref "Z5") (pin "2") (pinfunction "2_2") (pintype "passive"))
      (node (ref "Z5") (pin "4") (pinfunction "4_4") (pintype "passive"))
    )
    (net (code "126") (name "Net-(U1-EXTAL32_.)") (class "Default")
      (node (ref "C118") (pin "1") (pinfunction "1_1") (pintype "passive"))
      (node (ref "U1") (pin "41") (pinfunction "EXTAL32_._41") (pintype "bidirectional"))
      (node (ref "Z6") (pin "2") (pinfunction "2_2") (pintype "passive"))
    )
    (net (code "127") (name "Net-(U1-PTA0_._TSI0_CH1_._UART0_CTS#_._FTM0_CH5_._JTAG_TCLK{slash}SWD_CLK_._EZP_CLK)") (class "Default")
      (node (ref "U1") (pin "50") (pinfunction "PTA0_._TSI0_CH1_._UART0_CTS#_._FTM0_CH5_._JTAG_TCLK/SWD_CLK_._EZP_CLK_50") (pintype "bidirectional"))
      (node (ref "U14") (pin "4") (pinfunction "1A_4") (pintype "passive"))
    )
    (net (code "128") (name "Net-(U1-PTA1_._TSI0_CH2_._UART0_RX_._FTM0_CH6_._JTAG_TDI_._EZP_DI)") (class "Default")
      (node (ref "U1") (pin "51") (pinfunction "PTA1_._TSI0_CH2_._UART0_RX_._FTM0_CH6_._JTAG_TDI_._EZP_DI_51") (pintype "bidirectional"))
      (node (ref "U14") (pin "7") (pinfunction "2A_7") (pintype "passive"))
    )
    (net (code "129") (name "Net-(U1-PTA4{slash}LLWU_P3_._TSI0_CH5_._FTM0_CH1_._NMI#_._EZP_CS#)") (class "Default")
      (node (ref "U1") (pin "54") (pinfunction "PTA4/LLWU_P3_._TSI0_CH5_._FTM0_CH1_._NMI#_._EZP_CS#_54") (pintype "bidirectional"))
      (node (ref "U14") (pin "9") (pinfunction "3A_9") (pintype "passive"))
    )
    (net (code "130") (name "Net-(U1-VOUT33_.)") (class "Default")
      (node (ref "C111") (pin "1") (pinfunction "1_1") (pintype "passive"))
      (node (ref "R59") (pin "2") (pinfunction "2_2") (pintype "passive"))
      (node (ref "U1") (pin "21") (pinfunction "VOUT33_._21") (pintype "bidirectional"))
    )
    (net (code "131") (name "Net-(U1-VREFH_.)") (class "Default")
      (node (ref "C114") (pin "2") (pinfunction "2_2") (pintype "passive"))
      (node (ref "C115") (pin "1") (pinfunction "1_1") (pintype "passive"))
      (node (ref "L13") (pin "2") (pinfunction "2_2") (pintype "passive"))
      (node (ref "U1") (pin "32") (pinfunction "VREFH_._32") (pintype "power_in"))
    )
    (net (code "132") (name "Net-(U1-VREFL_.)") (class "Default")
      (node (ref "C114") (pin "1") (pinfunction "1_1") (pintype "passive"))
      (node (ref "C115") (pin "2") (pinfunction "2_2") (pintype "passive"))
      (node (ref "L14") (pin "2") (pinfunction "2_2") (pintype "passive"))
      (node (ref "U1") (pin "33") (pinfunction "VREFL_._33") (pintype "power_in"))
    )
    (net (code "133") (name "Net-(U1-VREF_OUT{slash}CMP1_IN5{slash}CMP0_IN5{slash}ADC1_SE18_.)") (class "Default")
      (node (ref "C116") (pin "1") (pinfunction "1_1") (pintype "passive"))
      (node (ref "U1") (pin "37") (pinfunction "VREF_OUT/CMP1_IN5/CMP0_IN5/ADC1_SE18_._37") (pintype "bidirectional"))
    )
    (net (code "134") (name "Net-(U1-XTAL32_.)") (class "Default")
      (node (ref "C117") (pin "1") (pinfunction "1_1") (pintype "passive"))
      (node (ref "U1") (pin "40") (pinfunction "XTAL32_._40") (pintype "bidirectional"))
      (node (ref "Z6") (pin "1") (pinfunction "1_1") (pintype "passive"))
    )
    (net (code "135") (name "Net-(X7-RESET)") (class "Default")
      (node (ref "D12") (pin "1") (pintype "passive"))
      (node (ref "X7") (pin "8") (pinfunction "RESET_8") (pintype "output"))
    )
    (net (code "136") (name "VBAT_2") (class "Default")
      (node (ref "U1") (pin "42") (pinfunction "VBAT_._42") (pintype "power_in"))
    )
    (net (code "137") (name "VDDA2") (class "Default")
      (node (ref "C112") (pin "2") (pinfunction "2_2") (pintype "passive"))
      (node (ref "C113") (pin "1") (pinfunction "1_1") (pintype "passive"))
      (node (ref "L12") (pin "1") (pinfunction "1_1") (pintype "passive"))
      (node (ref "L13") (pin "1") (pinfunction "1_1") (pintype "passive"))
      (node (ref "U1") (pin "31") (pinfunction "VDDA_._31") (pintype "power_in"))
    )
    (net (code "138") (name "VSSA2") (class "Default")
      (node (ref "C112") (pin "1") (pinfunction "1_1") (pintype "passive"))
      (node (ref "C113") (pin "2") (pinfunction "2_2") (pintype "passive"))
      (node (ref "C116") (pin "2") (pinfunction "2_2") (pintype "passive"))
      (node (ref "L14") (pin "1") (pinfunction "1_1") (pintype "passive"))
      (node (ref "L15") (pin "1") (pinfunction "1_1") (pintype "passive"))
      (node (ref "U1") (pin "34") (pinfunction "VSSA_._34") (pintype "power_in"))
    )
    (net (code "139") (name "unconnected-(X7-TRST-Pad2)") (class "Default")
      (node (ref "X7") (pin "2") (pinfunction "TRST_2") (pintype "passive"))
    )
  )
)
